# SensorBoardSchematic.net
KiCad netlist of a schematic drawn in Altium Designer
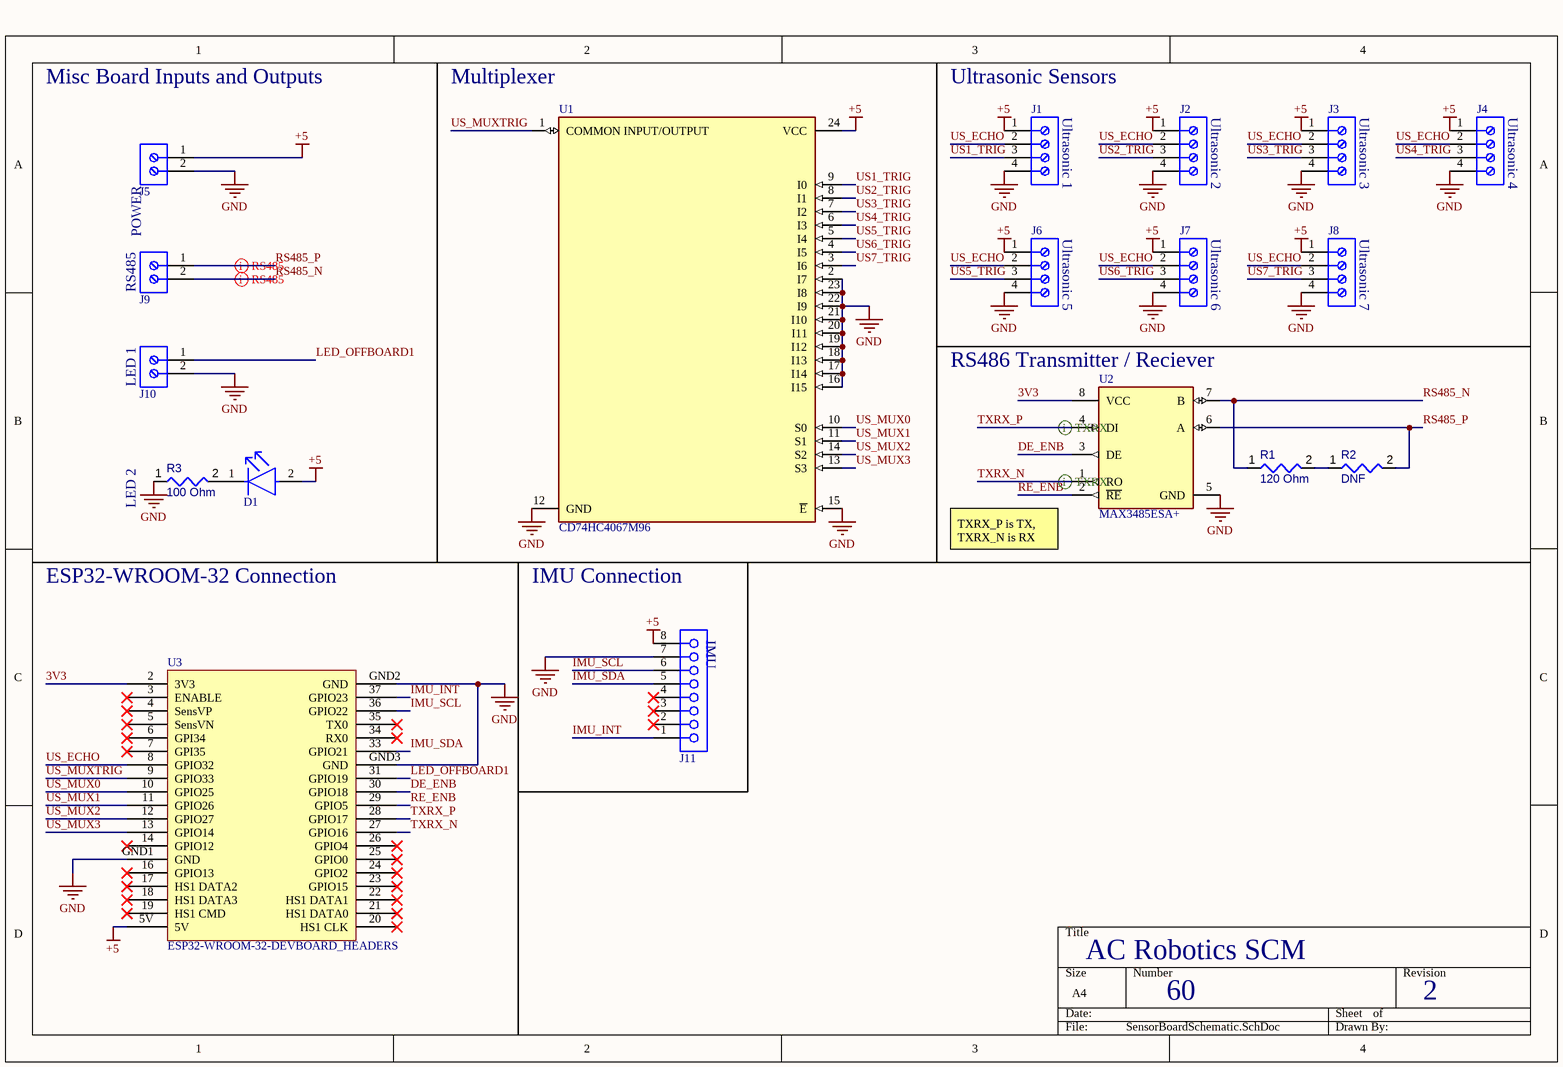
[diagram p0: SensorBoardSchematic.SchDoc]

(export (version "E")
  (design (tool "Eeschema 10.0.6"))
  (components
    (comp (ref "D1")
      (value "LTST-C190KFKT")
      (footprint "FP-LTST-C190KFKT-MFG")
      (description "LED ORANGE CLEAR CHIP SMD")
      (libsource (lib "Altium Content Vault") (part "8706943c75ba83719d021d2fdc84c58"))
    )
    (comp (ref "J1")
      (value "691709710304")
      (footprint "691709710304")
      (description "Serie 7097 - 5.00 mm Horizontal Entry SMT with Pressure Clamp WR-TBL, 4 pin")
      (fields (field (name "MANUFACTURER") "Wurth Elektronik") (field (name "PUBLISHER") "WurthElektronik"))
      (libsource (lib "Altium Content Vault") (part "WE-CN-1P-F-TB4"))
    )
    (comp (ref "J2")
      (value "691709710304")
      (footprint "691709710304")
      (description "Serie 7097 - 5.00 mm Horizontal Entry SMT with Pressure Clamp WR-TBL, 4 pin")
      (fields (field (name "MANUFACTURER") "Wurth Elektronik") (field (name "PUBLISHER") "WurthElektronik"))
      (libsource (lib "Altium Content Vault") (part "WE-CN-1P-F-TB4"))
    )
    (comp (ref "J3")
      (value "691709710304")
      (footprint "691709710304")
      (description "Serie 7097 - 5.00 mm Horizontal Entry SMT with Pressure Clamp WR-TBL, 4 pin")
      (fields (field (name "MANUFACTURER") "Wurth Elektronik") (field (name "PUBLISHER") "WurthElektronik"))
      (libsource (lib "Altium Content Vault") (part "WE-CN-1P-F-TB4"))
    )
    (comp (ref "J4")
      (value "691709710304")
      (footprint "691709710304")
      (description "Serie 7097 - 5.00 mm Horizontal Entry SMT with Pressure Clamp WR-TBL, 4 pin")
      (fields (field (name "MANUFACTURER") "Wurth Elektronik") (field (name "PUBLISHER") "WurthElektronik"))
      (libsource (lib "Altium Content Vault") (part "WE-CN-1P-F-TB4"))
    )
    (comp (ref "J5")
      (value "691102710002")
      (footprint "691102710002")
      (description "Series 102 - 5.00 mm Horizontal Entry Modular with Pressure Clamp WR-TBL, 2 pin")
      (fields (field (name "MANUFACTURER") "Wurth Elektronik") (field (name "PUBLISHER") "WurthElektronik"))
      (libsource (lib "Altium Content Vault") (part "WE-CN-1P-F-TB2"))
    )
    (comp (ref "J6")
      (value "691709710304")
      (footprint "691709710304")
      (description "Serie 7097 - 5.00 mm Horizontal Entry SMT with Pressure Clamp WR-TBL, 4 pin")
      (fields (field (name "MANUFACTURER") "Wurth Elektronik") (field (name "PUBLISHER") "WurthElektronik"))
      (libsource (lib "Altium Content Vault") (part "WE-CN-1P-F-TB4"))
    )
    (comp (ref "J7")
      (value "691709710304")
      (footprint "691709710304")
      (description "Serie 7097 - 5.00 mm Horizontal Entry SMT with Pressure Clamp WR-TBL, 4 pin")
      (fields (field (name "MANUFACTURER") "Wurth Elektronik") (field (name "PUBLISHER") "WurthElektronik"))
      (libsource (lib "Altium Content Vault") (part "WE-CN-1P-F-TB4"))
    )
    (comp (ref "J8")
      (value "691709710304")
      (footprint "691709710304")
      (description "Serie 7097 - 5.00 mm Horizontal Entry SMT with Pressure Clamp WR-TBL, 4 pin")
      (fields (field (name "MANUFACTURER") "Wurth Elektronik") (field (name "PUBLISHER") "WurthElektronik"))
      (libsource (lib "Altium Content Vault") (part "WE-CN-1P-F-TB4"))
    )
    (comp (ref "J9")
      (value "691102710002")
      (footprint "691102710002")
      (description "Series 102 - 5.00 mm Horizontal Entry Modular with Pressure Clamp WR-TBL, 2 pin")
      (fields (field (name "MANUFACTURER") "Wurth Elektronik") (field (name "PUBLISHER") "WurthElektronik"))
      (libsource (lib "Altium Content Vault") (part "WE-CN-1P-F-TB2"))
    )
    (comp (ref "J10")
      (value "691102710002")
      (footprint "691102710002")
      (description "Series 102 - 5.00 mm Horizontal Entry Modular with Pressure Clamp WR-TBL, 2 pin")
      (fields (field (name "MANUFACTURER") "Wurth Elektronik") (field (name "PUBLISHER") "WurthElektronik"))
      (libsource (lib "Altium Content Vault") (part "WE-CN-1P-F-TB2"))
    )
    (comp (ref "J11")
      (value "SSQ-108-01-T-S")
      (footprint "SMTC-SSQ-108-01-X-S")
      (description "SQ Post Socket, Through-hole, Vertical, -55 to 105 degC, 2.54 mm Pitch, 8-Pin, Female, RoHS")
      (fields (field (name "MANUFACTURER") "Samtec"))
      (libsource (lib "Altium Content Vault") (part "SMTC-SSQ-108-X-X-S-X"))
    )
    (comp (ref "R1")
      (value "120 Ohm")
      (footprint "RESC0603(1608)_L")
      (description "Jumper 0603")
      (libsource (lib "AC Robotics") (part "RES-2"))
    )
    (comp (ref "R2")
      (value "DNF")
      (footprint "RESC0603(1608)_L")
      (description "Jumper 0603")
      (libsource (lib "AC Robotics") (part "RES-2"))
    )
    (comp (ref "R3")
      (value "100 Ohm")
      (footprint "RESC0603(1608)_L")
      (description "Jumper 0603")
      (libsource (lib "AC Robotics") (part "RES-2"))
    )
    (comp (ref "U1")
      (value "CD74HC4067M96")
      (footprint "FP-DW0024A-MFG")
      (description "IC MUX/DEMUX 1X16 24SOIC")
      (fields
        (field (name "OCTOPART") "https://octopart.com/cd74hc4067m96-texas+instruments-722802")
        (field (name "MANUFACTURER") "Texas Instruments")
      )
      (libsource (lib "Altium Content Vault") (part "0e3014a41e7f600214dac1b4fa06845"))
    )
    (comp (ref "U2")
      (value "MAX3485ESA+")
      (footprint "FP-S8-5-MFG")
      (description "IC TXRX RS485/422 10MBPS 8SOIC")
      (fields
        (field (name "OCTOPART") "https://octopart.com/max3485esa%2B-maxim+integrated-39731860")
        (field (name "MANUFACTURER") "Maxim Integrated")
      )
      (libsource (lib "Altium Content Vault") (part "336746e10bf8cc649a8da99b4f6b1f2"))
    )
    (comp (ref "U3")
      (value "ESP32-WROOM-32-DEVBOARD_HEADERS")
      (footprint "ESP32-WROOM-32-DEVBOARD_HEADERS-Footprint-1")
      (description "Made by Aleksander")
      (libsource (lib "AC Robotics") (part "ESP32-WROOM-32-DEVBOARD_HEADERS-Symbol-1"))
    )
  )
  (nets
    (net (code "1") (name "+5") (class "Default")
      (node (ref "D1") (pin "2") (pinfunction "A_2") (pintype "passive"))
      (node (ref "J1") (pin "1") (pinfunction "1_1") (pintype "passive"))
      (node (ref "J11") (pin "8") (pinfunction "8_8") (pintype "passive"))
      (node (ref "J2") (pin "1") (pinfunction "1_1") (pintype "passive"))
      (node (ref "J3") (pin "1") (pinfunction "1_1") (pintype "passive"))
      (node (ref "J4") (pin "1") (pinfunction "1_1") (pintype "passive"))
      (node (ref "J5") (pin "1") (pinfunction "1_1") (pintype "passive"))
      (node (ref "J6") (pin "1") (pinfunction "1_1") (pintype "passive"))
      (node (ref "J7") (pin "1") (pinfunction "1_1") (pintype "passive"))
      (node (ref "J8") (pin "1") (pinfunction "1_1") (pintype "passive"))
      (node (ref "U1") (pin "24") (pinfunction "VCC_24") (pintype "power_in"))
      (node (ref "U3") (pin "5V") (pinfunction "5V_5V") (pintype "power_in"))
    )
    (net (code "2") (name "/3V3") (class "Default")
      (node (ref "U2") (pin "8") (pinfunction "VCC_8") (pintype "power_in"))
      (node (ref "U3") (pin "2") (pinfunction "3V3_2") (pintype "passive"))
    )
    (net (code "3") (name "/DE_ENB") (class "Default")
      (node (ref "U2") (pin "3") (pinfunction "DE_3") (pintype "output"))
      (node (ref "U3") (pin "30") (pinfunction "GPIO18_30") (pintype "passive"))
    )
    (net (code "4") (name "/IMU_INT") (class "Default")
      (node (ref "J11") (pin "1") (pinfunction "1_1") (pintype "passive"))
      (node (ref "U3") (pin "37") (pinfunction "GPIO23_37") (pintype "passive"))
    )
    (net (code "5") (name "/IMU_SCL") (class "Default")
      (node (ref "J11") (pin "6") (pinfunction "6_6") (pintype "passive"))
      (node (ref "U3") (pin "36") (pinfunction "GPIO22_36") (pintype "passive"))
    )
    (net (code "6") (name "/IMU_SDA") (class "Default")
      (node (ref "J11") (pin "5") (pinfunction "5_5") (pintype "passive"))
      (node (ref "U3") (pin "33") (pinfunction "GPIO21_33") (pintype "passive"))
    )
    (net (code "7") (name "/LED_OFFBOARD1") (class "Default")
      (node (ref "J10") (pin "1") (pinfunction "1_1") (pintype "passive"))
      (node (ref "U3") (pin "31") (pinfunction "GPIO19_31") (pintype "passive"))
    )
    (net (code "8") (name "/RE_ENB") (class "Default")
      (node (ref "U2") (pin "2") (pinfunction "~{RE}_2") (pintype "output"))
      (node (ref "U3") (pin "29") (pinfunction "GPIO5_29") (pintype "passive"))
    )
    (net (code "9") (name "/RS485_N") (class "Default")
      (node (ref "J9") (pin "2") (pinfunction "2_2") (pintype "passive"))
      (node (ref "R1") (pin "1") (pinfunction "1_1") (pintype "passive"))
      (node (ref "U2") (pin "7") (pinfunction "B_7") (pintype "bidirectional"))
    )
    (net (code "10") (name "/RS485_P") (class "Default")
      (node (ref "J9") (pin "1") (pinfunction "1_1") (pintype "passive"))
      (node (ref "R2") (pin "2") (pinfunction "2_2") (pintype "passive"))
      (node (ref "U2") (pin "6") (pinfunction "A_6") (pintype "bidirectional"))
    )
    (net (code "11") (name "/TXRX_N") (class "Default")
      (node (ref "U2") (pin "1") (pinfunction "RO_1") (pintype "output"))
      (node (ref "U3") (pin "27") (pinfunction "GPIO16_27") (pintype "passive"))
    )
    (net (code "12") (name "/TXRX_P") (class "Default")
      (node (ref "U2") (pin "4") (pinfunction "DI_4") (pintype "input"))
      (node (ref "U3") (pin "28") (pinfunction "GPIO17_28") (pintype "passive"))
    )
    (net (code "13") (name "/US1_TRIG") (class "Default")
      (node (ref "J1") (pin "3") (pinfunction "3_3") (pintype "passive"))
      (node (ref "U1") (pin "9") (pinfunction "I0_9") (pintype "input"))
    )
    (net (code "14") (name "/US2_TRIG") (class "Default")
      (node (ref "J2") (pin "3") (pinfunction "3_3") (pintype "passive"))
      (node (ref "U1") (pin "8") (pinfunction "I1_8") (pintype "input"))
    )
    (net (code "15") (name "/US3_TRIG") (class "Default")
      (node (ref "J3") (pin "3") (pinfunction "3_3") (pintype "passive"))
      (node (ref "U1") (pin "7") (pinfunction "I2_7") (pintype "input"))
    )
    (net (code "16") (name "/US4_TRIG") (class "Default")
      (node (ref "J4") (pin "3") (pinfunction "3_3") (pintype "passive"))
      (node (ref "U1") (pin "6") (pinfunction "I3_6") (pintype "input"))
    )
    (net (code "17") (name "/US5_TRIG") (class "Default")
      (node (ref "J6") (pin "3") (pinfunction "3_3") (pintype "passive"))
      (node (ref "U1") (pin "5") (pinfunction "I4_5") (pintype "input"))
    )
    (net (code "18") (name "/US6_TRIG") (class "Default")
      (node (ref "J7") (pin "3") (pinfunction "3_3") (pintype "passive"))
      (node (ref "U1") (pin "4") (pinfunction "I5_4") (pintype "input"))
    )
    (net (code "19") (name "/US7_TRIG") (class "Default")
      (node (ref "J8") (pin "3") (pinfunction "3_3") (pintype "passive"))
      (node (ref "U1") (pin "3") (pinfunction "I6_3") (pintype "input"))
    )
    (net (code "20") (name "/US_ECHO") (class "Default")
      (node (ref "J1") (pin "2") (pinfunction "2_2") (pintype "passive"))
      (node (ref "J2") (pin "2") (pinfunction "2_2") (pintype "passive"))
      (node (ref "J3") (pin "2") (pinfunction "2_2") (pintype "passive"))
      (node (ref "J4") (pin "2") (pinfunction "2_2") (pintype "passive"))
      (node (ref "J6") (pin "2") (pinfunction "2_2") (pintype "passive"))
      (node (ref "J7") (pin "2") (pinfunction "2_2") (pintype "passive"))
      (node (ref "J8") (pin "2") (pinfunction "2_2") (pintype "passive"))
      (node (ref "U3") (pin "8") (pinfunction "GPIO32_8") (pintype "passive"))
    )
    (net (code "21") (name "/US_MUX0") (class "Default")
      (node (ref "U1") (pin "10") (pinfunction "S0_10") (pintype "input"))
      (node (ref "U3") (pin "10") (pinfunction "GPIO25_10") (pintype "passive"))
    )
    (net (code "22") (name "/US_MUX1") (class "Default")
      (node (ref "U1") (pin "11") (pinfunction "S1_11") (pintype "input"))
      (node (ref "U3") (pin "11") (pinfunction "GPIO26_11") (pintype "passive"))
    )
    (net (code "23") (name "/US_MUX2") (class "Default")
      (node (ref "U1") (pin "14") (pinfunction "S2_14") (pintype "input"))
      (node (ref "U3") (pin "12") (pinfunction "GPIO27_12") (pintype "passive"))
    )
    (net (code "24") (name "/US_MUX3") (class "Default")
      (node (ref "U1") (pin "13") (pinfunction "S3_13") (pintype "input"))
      (node (ref "U3") (pin "13") (pinfunction "GPIO14_13") (pintype "passive"))
    )
    (net (code "25") (name "/US_MUXTRIG") (class "Default")
      (node (ref "U1") (pin "1") (pinfunction "COMMON_INPUT/OUTPUT_1") (pintype "bidirectional"))
      (node (ref "U3") (pin "9") (pinfunction "GPIO33_9") (pintype "passive"))
    )
    (net (code "26") (name "GND") (class "Default")
      (node (ref "J1") (pin "4") (pinfunction "4_4") (pintype "passive"))
      (node (ref "J10") (pin "2") (pinfunction "2_2") (pintype "passive"))
      (node (ref "J11") (pin "7") (pinfunction "7_7") (pintype "passive"))
      (node (ref "J2") (pin "4") (pinfunction "4_4") (pintype "passive"))
      (node (ref "J3") (pin "4") (pinfunction "4_4") (pintype "passive"))
      (node (ref "J4") (pin "4") (pinfunction "4_4") (pintype "passive"))
      (node (ref "J5") (pin "2") (pinfunction "2_2") (pintype "passive"))
      (node (ref "J6") (pin "4") (pinfunction "4_4") (pintype "passive"))
      (node (ref "J7") (pin "4") (pinfunction "4_4") (pintype "passive"))
      (node (ref "J8") (pin "4") (pinfunction "4_4") (pintype "passive"))
      (node (ref "R3") (pin "1") (pinfunction "1_1") (pintype "passive"))
      (node (ref "U1") (pin "12") (pinfunction "GND_12") (pintype "power_in"))
      (node (ref "U1") (pin "15") (pinfunction "~{E}_15") (pintype "input"))
      (node (ref "U1") (pin "16") (pinfunction "I15_16") (pintype "input"))
      (node (ref "U1") (pin "17") (pinfunction "I14_17") (pintype "input"))
      (node (ref "U1") (pin "18") (pinfunction "I13_18") (pintype "input"))
      (node (ref "U1") (pin "19") (pinfunction "I12_19") (pintype "input"))
      (node (ref "U1") (pin "2") (pinfunction "I7_2") (pintype "input"))
      (node (ref "U1") (pin "20") (pinfunction "I11_20") (pintype "input"))
      (node (ref "U1") (pin "21") (pinfunction "I10_21") (pintype "input"))
      (node (ref "U1") (pin "22") (pinfunction "I9_22") (pintype "input"))
      (node (ref "U1") (pin "23") (pinfunction "I8_23") (pintype "input"))
      (node (ref "U2") (pin "5") (pinfunction "GND_5") (pintype "power_in"))
      (node (ref "U3") (pin "GND1") (pinfunction "GND_GND1") (pintype "power_in"))
      (node (ref "U3") (pin "GND2") (pinfunction "GND_GND2") (pintype "passive"))
      (node (ref "U3") (pin "GND3") (pinfunction "GND_GND3") (pintype "passive"))
    )
    (net (code "27") (name "Net-(D1-C)") (class "Default")
      (node (ref "D1") (pin "1") (pinfunction "C_1") (pintype "passive"))
      (node (ref "R3") (pin "2") (pinfunction "2_2") (pintype "passive"))
    )
    (net (code "28") (name "Net-(R1-Pad2)") (class "Default")
      (node (ref "R1") (pin "2") (pinfunction "2_2") (pintype "passive"))
      (node (ref "R2") (pin "1") (pinfunction "1_1") (pintype "passive"))
    )
    (net (code "29") (name "unconnected-(J11-Pad2)") (class "Default")
      (node (ref "J11") (pin "2") (pinfunction "2_2") (pintype "passive+no_connect"))
    )
    (net (code "30") (name "unconnected-(J11-Pad3)") (class "Default")
      (node (ref "J11") (pin "3") (pinfunction "3_3") (pintype "passive+no_connect"))
    )
    (net (code "31") (name "unconnected-(J11-Pad4)") (class "Default")
      (node (ref "J11") (pin "4") (pinfunction "4_4") (pintype "passive+no_connect"))
    )
    (net (code "32") (name "unconnected-(U3-ENABLE-Pad3)") (class "Default")
      (node (ref "U3") (pin "3") (pinfunction "ENABLE_3") (pintype "passive+no_connect"))
    )
    (net (code "33") (name "unconnected-(U3-GPI34-Pad6)") (class "Default")
      (node (ref "U3") (pin "6") (pinfunction "GPI34_6") (pintype "passive+no_connect"))
    )
    (net (code "34") (name "unconnected-(U3-GPI35-Pad7)") (class "Default")
      (node (ref "U3") (pin "7") (pinfunction "GPI35_7") (pintype "passive+no_connect"))
    )
    (net (code "35") (name "unconnected-(U3-GPIO0-Pad25)") (class "Default")
      (node (ref "U3") (pin "25") (pinfunction "GPIO0_25") (pintype "power_in+no_connect"))
    )
    (net (code "36") (name "unconnected-(U3-GPIO2-Pad24)") (class "Default")
      (node (ref "U3") (pin "24") (pinfunction "GPIO2_24") (pintype "passive+no_connect"))
    )
    (net (code "37") (name "unconnected-(U3-GPIO4-Pad26)") (class "Default")
      (node (ref "U3") (pin "26") (pinfunction "GPIO4_26") (pintype "passive+no_connect"))
    )
    (net (code "38") (name "unconnected-(U3-GPIO12-Pad14)") (class "Default")
      (node (ref "U3") (pin "14") (pinfunction "GPIO12_14") (pintype "passive+no_connect"))
    )
    (net (code "39") (name "unconnected-(U3-GPIO13-Pad16)") (class "Default")
      (node (ref "U3") (pin "16") (pinfunction "GPIO13_16") (pintype "power_in+no_connect"))
    )
    (net (code "40") (name "unconnected-(U3-GPIO15-Pad23)") (class "Default")
      (node (ref "U3") (pin "23") (pinfunction "GPIO15_23") (pintype "passive+no_connect"))
    )
    (net (code "41") (name "unconnected-(U3-HS1_CLK-Pad20)") (class "Default")
      (node (ref "U3") (pin "20") (pinfunction "HS1_CLK_20") (pintype "passive+no_connect"))
    )
    (net (code "42") (name "unconnected-(U3-HS1_CMD-Pad19)") (class "Default")
      (node (ref "U3") (pin "19") (pinfunction "HS1_CMD_19") (pintype "power_in+no_connect"))
    )
    (net (code "43") (name "unconnected-(U3-HS1_DATA0-Pad21)") (class "Default")
      (node (ref "U3") (pin "21") (pinfunction "HS1_DATA0_21") (pintype "power_in+no_connect"))
    )
    (net (code "44") (name "unconnected-(U3-HS1_DATA1-Pad22)") (class "Default")
      (node (ref "U3") (pin "22") (pinfunction "HS1_DATA1_22") (pintype "passive+no_connect"))
    )
    (net (code "45") (name "unconnected-(U3-HS1_DATA2-Pad17)") (class "Default")
      (node (ref "U3") (pin "17") (pinfunction "HS1_DATA2_17") (pintype "passive+no_connect"))
    )
    (net (code "46") (name "unconnected-(U3-HS1_DATA3-Pad18)") (class "Default")
      (node (ref "U3") (pin "18") (pinfunction "HS1_DATA3_18") (pintype "passive+no_connect"))
    )
    (net (code "47") (name "unconnected-(U3-RX0-Pad34)") (class "Default")
      (node (ref "U3") (pin "34") (pinfunction "RX0_34") (pintype "passive+no_connect"))
    )
    (net (code "48") (name "unconnected-(U3-SensVN-Pad5)") (class "Default")
      (node (ref "U3") (pin "5") (pinfunction "SensVN_5") (pintype "passive+no_connect"))
    )
    (net (code "49") (name "unconnected-(U3-SensVP-Pad4)") (class "Default")
      (node (ref "U3") (pin "4") (pinfunction "SensVP_4") (pintype "passive+no_connect"))
    )
    (net (code "50") (name "unconnected-(U3-TX0-Pad35)") (class "Default")
      (node (ref "U3") (pin "35") (pinfunction "TX0_35") (pintype "passive+no_connect"))
    )
  )
)
